# Microcontrolador.net
KiCad netlist of a schematic drawn in Altium Designer
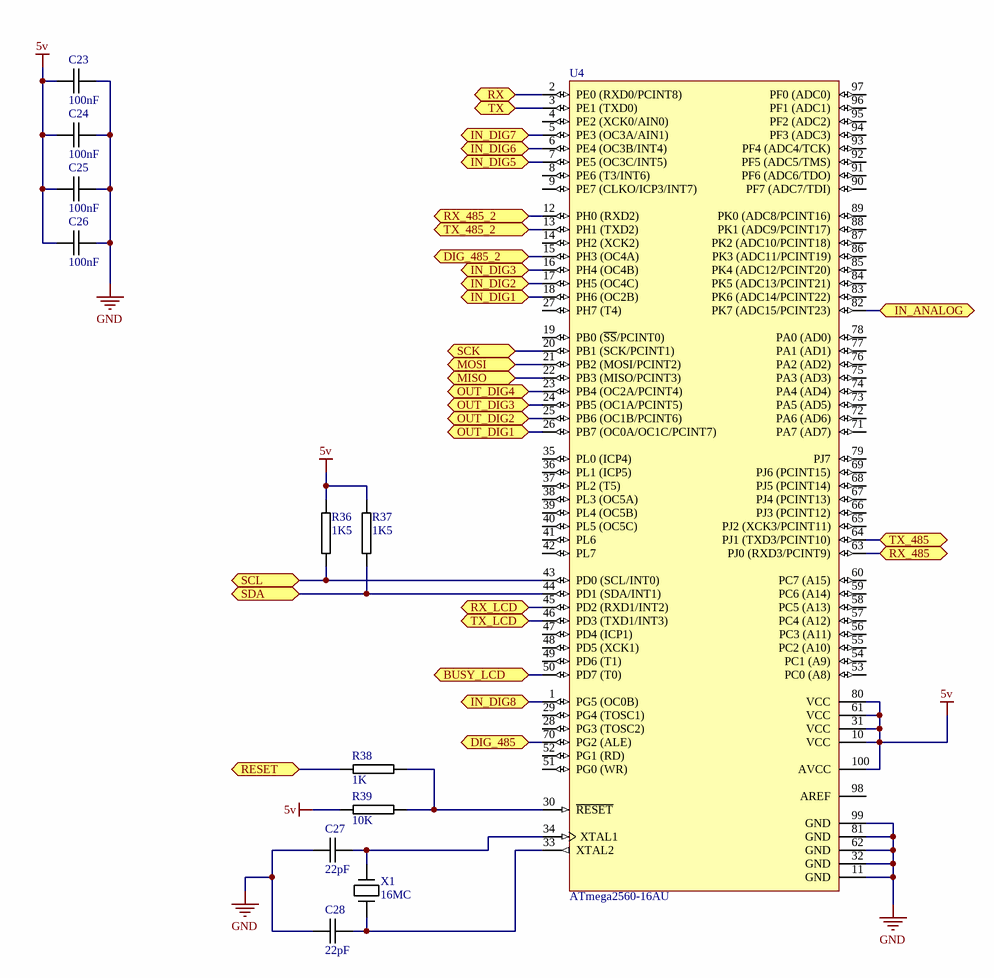
[diagram p0: Microcontrolador.SchDoc]

(export (version "E")
  (design (tool "Eeschema 10.0.6"))
  (components
    (comp (ref "C23")
      (value "100nF")
      (footprint "0805C-TBD")
      (description "CAPACITOR 0805 CERAMIC")
      (libsource (lib "vh_altium_library") (part "0805C-100nF-25V-X7R-MUR"))
    )
    (comp (ref "C24")
      (value "100nF")
      (footprint "0805C-TBD")
      (description "CAPACITOR 0805 CERAMIC")
      (libsource (lib "vh_altium_library") (part "0805C-100nF-25V-X7R-MUR"))
    )
    (comp (ref "C25")
      (value "100nF")
      (footprint "0805C-TBD")
      (description "CAPACITOR 0805 CERAMIC")
      (libsource (lib "vh_altium_library") (part "0805C-100nF-25V-X7R-MUR"))
    )
    (comp (ref "C26")
      (value "100nF")
      (footprint "0805C-TBD")
      (description "CAPACITOR 0805 CERAMIC")
      (libsource (lib "vh_altium_library") (part "0805C-100nF-25V-X7R-MUR"))
    )
    (comp (ref "C27")
      (value "22pF")
      (footprint "0603C-GENERIC")
      (description "CAPACITOR 0603 CERAMIC")
      (fields (field (name "TOLERANCE") "±5%") (field (name "MANUFACTURER PART NUMBER") "ECJ-1VC1H220J"))
      (libsource (lib "vh_altium_library") (part "0603C-22PF-50V-C0G-PAN"))
    )
    (comp (ref "C28")
      (value "22pF")
      (footprint "0603C-GENERIC")
      (description "CAPACITOR 0603 CERAMIC")
      (fields (field (name "TOLERANCE") "±5%") (field (name "MANUFACTURER PART NUMBER") "ECJ-1VC1H220J"))
      (libsource (lib "vh_altium_library") (part "0603C-22PF-50V-C0G-PAN"))
    )
    (comp (ref "R36")
      (value "1K5")
      (footprint "0805R-1K5")
      (description "RESISTOR 0805 1/4 WATT THIN FILM")
      (libsource (lib "vh_altium_library") (part "0805R-1K5"))
    )
    (comp (ref "R37")
      (value "1K5")
      (footprint "0805R-1K5")
      (description "RESISTOR 0805 1/4 WATT THIN FILM")
      (libsource (lib "vh_altium_library") (part "0805R-1K5"))
    )
    (comp (ref "R38")
      (value "1K")
      (footprint "0805R-1K")
      (description "RESISTOR 0805 1/4 WATT THIN FILM")
      (libsource (lib "vh_altium_library") (part "0805R-1K"))
    )
    (comp (ref "R39")
      (value "10K")
      (footprint "0805R-10K")
      (description "RESISTOR 0805 1/4 WATT THIN FILM")
      (libsource (lib "vh_altium_library") (part "0805R-10K"))
    )
    (comp (ref "U4")
      (value "ATmega2560-16AU")
      (footprint "100A_N")
      (libsource (lib "Atmel Microcontroller megaAVR") (part "ATmega2560-16AU"))
    )
    (comp (ref "X1")
      (value "16MC")
      (footprint "XTAL-RU49/4")
      (description "16MHZ CRSYTAL HC49US")
      (libsource (lib "vh_altium_library") (part "16MC-HC49US"))
    )
  )
  (nets
    (net (code "1") (name "/BUSY_LCD") (class "Default")
      (node (ref "U4") (pin "50") (pinfunction "PD7_(T0)_50") (pintype "bidirectional"))
    )
    (net (code "2") (name "/DIG_485") (class "Default")
      (node (ref "U4") (pin "70") (pinfunction "PG2_(ALE)_70") (pintype "bidirectional"))
    )
    (net (code "3") (name "/DIG_485_2") (class "Default")
      (node (ref "U4") (pin "15") (pinfunction "PH3_(OC4A)_15") (pintype "bidirectional"))
    )
    (net (code "4") (name "/IN_ANALOG") (class "Default")
      (node (ref "U4") (pin "82") (pinfunction "PK7_(ADC15/PCINT23)_82") (pintype "bidirectional"))
    )
    (net (code "5") (name "/IN_DIG1") (class "Default")
      (node (ref "U4") (pin "18") (pinfunction "PH6_(OC2B)_18") (pintype "bidirectional"))
    )
    (net (code "6") (name "/IN_DIG2") (class "Default")
      (node (ref "U4") (pin "17") (pinfunction "PH5_(OC4C)_17") (pintype "bidirectional"))
    )
    (net (code "7") (name "/IN_DIG3") (class "Default")
      (node (ref "U4") (pin "16") (pinfunction "PH4_(OC4B)_16") (pintype "bidirectional"))
    )
    (net (code "8") (name "/IN_DIG5") (class "Default")
      (node (ref "U4") (pin "7") (pinfunction "PE5_(OC3C/INT5)_7") (pintype "bidirectional"))
    )
    (net (code "9") (name "/IN_DIG6") (class "Default")
      (node (ref "U4") (pin "6") (pinfunction "PE4_(OC3B/INT4)_6") (pintype "bidirectional"))
    )
    (net (code "10") (name "/IN_DIG7") (class "Default")
      (node (ref "U4") (pin "5") (pinfunction "PE3_(OC3A/AIN1)_5") (pintype "bidirectional"))
    )
    (net (code "11") (name "/IN_DIG8") (class "Default")
      (node (ref "U4") (pin "1") (pinfunction "PG5_(OC0B)_1") (pintype "bidirectional"))
    )
    (net (code "12") (name "/MISO") (class "Default")
      (node (ref "U4") (pin "22") (pinfunction "PB3_(MISO/PCINT3)_22") (pintype "bidirectional"))
    )
    (net (code "13") (name "/MOSI") (class "Default")
      (node (ref "U4") (pin "21") (pinfunction "PB2_(MOSI/PCINT2)_21") (pintype "bidirectional"))
    )
    (net (code "14") (name "/OUT_DIG1") (class "Default")
      (node (ref "U4") (pin "26") (pinfunction "PB7_(OC0A/OC1C/PCINT7)_26") (pintype "bidirectional"))
    )
    (net (code "15") (name "/OUT_DIG2") (class "Default")
      (node (ref "U4") (pin "25") (pinfunction "PB6_(OC1B/PCINT6)_25") (pintype "bidirectional"))
    )
    (net (code "16") (name "/OUT_DIG3") (class "Default")
      (node (ref "U4") (pin "24") (pinfunction "PB5_(OC1A/PCINT5)_24") (pintype "bidirectional"))
    )
    (net (code "17") (name "/OUT_DIG4") (class "Default")
      (node (ref "U4") (pin "23") (pinfunction "PB4_(OC2A/PCINT4)_23") (pintype "bidirectional"))
    )
    (net (code "18") (name "/RESET") (class "Default") (node (ref "R38") (pin "1") (pintype "passive")))
    (net (code "19") (name "/RX") (class "Default")
      (node (ref "U4") (pin "2") (pinfunction "PE0_(RXD0/PCINT8)_2") (pintype "bidirectional"))
    )
    (net (code "20") (name "/RX_485") (class "Default")
      (node (ref "U4") (pin "63") (pinfunction "PJ0_(RXD3/PCINT9)_63") (pintype "bidirectional"))
    )
    (net (code "21") (name "/RX_485_2") (class "Default")
      (node (ref "U4") (pin "12") (pinfunction "PH0_(RXD2)_12") (pintype "bidirectional"))
    )
    (net (code "22") (name "/RX_LCD") (class "Default")
      (node (ref "U4") (pin "45") (pinfunction "PD2_(RXD1/INT2)_45") (pintype "bidirectional"))
    )
    (net (code "23") (name "/SCK") (class "Default")
      (node (ref "U4") (pin "20") (pinfunction "PB1_(SCK/PCINT1)_20") (pintype "bidirectional"))
    )
    (net (code "24") (name "/SCL") (class "Default")
      (node (ref "R36") (pin "2") (pintype "passive"))
      (node (ref "U4") (pin "43") (pinfunction "PD0_(SCL/INT0)_43") (pintype "bidirectional"))
    )
    (net (code "25") (name "/SDA") (class "Default")
      (node (ref "R37") (pin "2") (pintype "passive"))
      (node (ref "U4") (pin "44") (pinfunction "PD1_(SDA/INT1)_44") (pintype "bidirectional"))
    )
    (net (code "26") (name "/TX") (class "Default")
      (node (ref "U4") (pin "3") (pinfunction "PE1_(TXD0)_3") (pintype "bidirectional"))
    )
    (net (code "27") (name "/TX_485") (class "Default")
      (node (ref "U4") (pin "64") (pinfunction "PJ1_(TXD3/PCINT10)_64") (pintype "bidirectional"))
    )
    (net (code "28") (name "/TX_485_2") (class "Default")
      (node (ref "U4") (pin "13") (pinfunction "PH1_(TXD2)_13") (pintype "bidirectional"))
    )
    (net (code "29") (name "/TX_LCD") (class "Default")
      (node (ref "U4") (pin "46") (pinfunction "PD3_(TXD1/INT3)_46") (pintype "bidirectional"))
    )
    (net (code "30") (name "5v") (class "Default")
      (node (ref "C23") (pin "1") (pintype "passive"))
      (node (ref "C24") (pin "1") (pintype "passive"))
      (node (ref "C25") (pin "1") (pintype "passive"))
      (node (ref "C26") (pin "1") (pintype "passive"))
      (node (ref "R36") (pin "1") (pintype "passive"))
      (node (ref "R37") (pin "1") (pintype "passive"))
      (node (ref "R39") (pin "1") (pintype "passive"))
      (node (ref "U4") (pin "10") (pinfunction "VCC_10") (pintype "power_in"))
      (node (ref "U4") (pin "100") (pinfunction "AVCC_100") (pintype "power_in"))
      (node (ref "U4") (pin "31") (pinfunction "VCC_31") (pintype "power_in"))
      (node (ref "U4") (pin "61") (pinfunction "VCC_61") (pintype "power_in"))
      (node (ref "U4") (pin "80") (pinfunction "VCC_80") (pintype "power_in"))
    )
    (net (code "31") (name "GND") (class "Default")
      (node (ref "C23") (pin "2") (pintype "passive"))
      (node (ref "C24") (pin "2") (pintype "passive"))
      (node (ref "C25") (pin "2") (pintype "passive"))
      (node (ref "C26") (pin "2") (pintype "passive"))
      (node (ref "C27") (pin "1") (pintype "passive"))
      (node (ref "C28") (pin "1") (pintype "passive"))
      (node (ref "U4") (pin "11") (pinfunction "GND_11") (pintype "power_in"))
      (node (ref "U4") (pin "32") (pinfunction "GND_32") (pintype "power_in"))
      (node (ref "U4") (pin "62") (pinfunction "GND_62") (pintype "power_in"))
      (node (ref "U4") (pin "81") (pinfunction "GND_81") (pintype "power_in"))
      (node (ref "U4") (pin "99") (pinfunction "GND_99") (pintype "power_in"))
    )
    (net (code "32") (name "Net-(U4-XTAL1)") (class "Default")
      (node (ref "C27") (pin "2") (pintype "passive"))
      (node (ref "U4") (pin "34") (pinfunction "XTAL1_34") (pintype "input"))
      (node (ref "X1") (pin "1") (pintype "passive"))
    )
    (net (code "33") (name "Net-(U4-XTAL2)") (class "Default")
      (node (ref "C28") (pin "2") (pintype "passive"))
      (node (ref "U4") (pin "33") (pinfunction "XTAL2_33") (pintype "output"))
      (node (ref "X1") (pin "2") (pintype "passive"))
    )
    (net (code "34") (name "Net-(U4-~{RESET})") (class "Default")
      (node (ref "R38") (pin "2") (pintype "passive"))
      (node (ref "R39") (pin "2") (pintype "passive"))
      (node (ref "U4") (pin "30") (pinfunction "~{RESET}_30") (pintype "input"))
    )
    (net (code "35") (name "unconnected-(U4-AREF-Pad98)") (class "Default")
      (node (ref "U4") (pin "98") (pinfunction "AREF_98") (pintype "power_in"))
    )
    (net (code "36") (name "unconnected-(U4-PA0_(AD0)-Pad78)") (class "Default")
      (node (ref "U4") (pin "78") (pinfunction "PA0_(AD0)_78") (pintype "bidirectional"))
    )
    (net (code "37") (name "unconnected-(U4-PA1_(AD1)-Pad77)") (class "Default")
      (node (ref "U4") (pin "77") (pinfunction "PA1_(AD1)_77") (pintype "bidirectional"))
    )
    (net (code "38") (name "unconnected-(U4-PA2_(AD2)-Pad76)") (class "Default")
      (node (ref "U4") (pin "76") (pinfunction "PA2_(AD2)_76") (pintype "bidirectional"))
    )
    (net (code "39") (name "unconnected-(U4-PA3_(AD3)-Pad75)") (class "Default")
      (node (ref "U4") (pin "75") (pinfunction "PA3_(AD3)_75") (pintype "bidirectional"))
    )
    (net (code "40") (name "unconnected-(U4-PA4_(AD4)-Pad74)") (class "Default")
      (node (ref "U4") (pin "74") (pinfunction "PA4_(AD4)_74") (pintype "bidirectional"))
    )
    (net (code "41") (name "unconnected-(U4-PA5_(AD5)-Pad73)") (class "Default")
      (node (ref "U4") (pin "73") (pinfunction "PA5_(AD5)_73") (pintype "bidirectional"))
    )
    (net (code "42") (name "unconnected-(U4-PA6_(AD6)-Pad72)") (class "Default")
      (node (ref "U4") (pin "72") (pinfunction "PA6_(AD6)_72") (pintype "bidirectional"))
    )
    (net (code "43") (name "unconnected-(U4-PA7_(AD7)-Pad71)") (class "Default")
      (node (ref "U4") (pin "71") (pinfunction "PA7_(AD7)_71") (pintype "bidirectional"))
    )
    (net (code "44") (name "unconnected-(U4-PB0_(~{SS}{slash}PCINT0)-Pad19)") (class "Default")
      (node (ref "U4") (pin "19") (pinfunction "PB0_(~{SS}/PCINT0)_19") (pintype "bidirectional"))
    )
    (net (code "45") (name "unconnected-(U4-PC0_(A8)-Pad53)") (class "Default")
      (node (ref "U4") (pin "53") (pinfunction "PC0_(A8)_53") (pintype "bidirectional"))
    )
    (net (code "46") (name "unconnected-(U4-PC1_(A9)-Pad54)") (class "Default")
      (node (ref "U4") (pin "54") (pinfunction "PC1_(A9)_54") (pintype "bidirectional"))
    )
    (net (code "47") (name "unconnected-(U4-PC2_(A10)-Pad55)") (class "Default")
      (node (ref "U4") (pin "55") (pinfunction "PC2_(A10)_55") (pintype "bidirectional"))
    )
    (net (code "48") (name "unconnected-(U4-PC3_(A11)-Pad56)") (class "Default")
      (node (ref "U4") (pin "56") (pinfunction "PC3_(A11)_56") (pintype "bidirectional"))
    )
    (net (code "49") (name "unconnected-(U4-PC4_(A12)-Pad57)") (class "Default")
      (node (ref "U4") (pin "57") (pinfunction "PC4_(A12)_57") (pintype "bidirectional"))
    )
    (net (code "50") (name "unconnected-(U4-PC5_(A13)-Pad58)") (class "Default")
      (node (ref "U4") (pin "58") (pinfunction "PC5_(A13)_58") (pintype "bidirectional"))
    )
    (net (code "51") (name "unconnected-(U4-PC6_(A14)-Pad59)") (class "Default")
      (node (ref "U4") (pin "59") (pinfunction "PC6_(A14)_59") (pintype "bidirectional"))
    )
    (net (code "52") (name "unconnected-(U4-PC7_(A15)-Pad60)") (class "Default")
      (node (ref "U4") (pin "60") (pinfunction "PC7_(A15)_60") (pintype "bidirectional"))
    )
    (net (code "53") (name "unconnected-(U4-PD4_(ICP1)-Pad47)") (class "Default")
      (node (ref "U4") (pin "47") (pinfunction "PD4_(ICP1)_47") (pintype "bidirectional"))
    )
    (net (code "54") (name "unconnected-(U4-PD5_(XCK1)-Pad48)") (class "Default")
      (node (ref "U4") (pin "48") (pinfunction "PD5_(XCK1)_48") (pintype "bidirectional"))
    )
    (net (code "55") (name "unconnected-(U4-PD6_(T1)-Pad49)") (class "Default")
      (node (ref "U4") (pin "49") (pinfunction "PD6_(T1)_49") (pintype "bidirectional"))
    )
    (net (code "56") (name "unconnected-(U4-PE2_(XCK0{slash}AIN0)-Pad4)") (class "Default")
      (node (ref "U4") (pin "4") (pinfunction "PE2_(XCK0/AIN0)_4") (pintype "bidirectional"))
    )
    (net (code "57") (name "unconnected-(U4-PE6_(T3{slash}INT6)-Pad8)") (class "Default")
      (node (ref "U4") (pin "8") (pinfunction "PE6_(T3/INT6)_8") (pintype "bidirectional"))
    )
    (net (code "58") (name "unconnected-(U4-PE7_(CLKO{slash}ICP3{slash}INT7)-Pad9)") (class "Default")
      (node (ref "U4") (pin "9") (pinfunction "PE7_(CLKO/ICP3/INT7)_9") (pintype "bidirectional"))
    )
    (net (code "59") (name "unconnected-(U4-PF0_(ADC0)-Pad97)") (class "Default")
      (node (ref "U4") (pin "97") (pinfunction "PF0_(ADC0)_97") (pintype "bidirectional"))
    )
    (net (code "60") (name "unconnected-(U4-PF1_(ADC1)-Pad96)") (class "Default")
      (node (ref "U4") (pin "96") (pinfunction "PF1_(ADC1)_96") (pintype "bidirectional"))
    )
    (net (code "61") (name "unconnected-(U4-PF2_(ADC2)-Pad95)") (class "Default")
      (node (ref "U4") (pin "95") (pinfunction "PF2_(ADC2)_95") (pintype "bidirectional"))
    )
    (net (code "62") (name "unconnected-(U4-PF3_(ADC3)-Pad94)") (class "Default")
      (node (ref "U4") (pin "94") (pinfunction "PF3_(ADC3)_94") (pintype "bidirectional"))
    )
    (net (code "63") (name "unconnected-(U4-PF4_(ADC4{slash}TCK)-Pad93)") (class "Default")
      (node (ref "U4") (pin "93") (pinfunction "PF4_(ADC4/TCK)_93") (pintype "bidirectional"))
    )
    (net (code "64") (name "unconnected-(U4-PF5_(ADC5{slash}TMS)-Pad92)") (class "Default")
      (node (ref "U4") (pin "92") (pinfunction "PF5_(ADC5/TMS)_92") (pintype "bidirectional"))
    )
    (net (code "65") (name "unconnected-(U4-PF6_(ADC6{slash}TDO)-Pad91)") (class "Default")
      (node (ref "U4") (pin "91") (pinfunction "PF6_(ADC6/TDO)_91") (pintype "bidirectional"))
    )
    (net (code "66") (name "unconnected-(U4-PF7_(ADC7{slash}TDI)-Pad90)") (class "Default")
      (node (ref "U4") (pin "90") (pinfunction "PF7_(ADC7/TDI)_90") (pintype "bidirectional"))
    )
    (net (code "67") (name "unconnected-(U4-PG0_(WR)-Pad51)") (class "Default")
      (node (ref "U4") (pin "51") (pinfunction "PG0_(WR)_51") (pintype "bidirectional"))
    )
    (net (code "68") (name "unconnected-(U4-PG1_(RD)-Pad52)") (class "Default")
      (node (ref "U4") (pin "52") (pinfunction "PG1_(RD)_52") (pintype "bidirectional"))
    )
    (net (code "69") (name "unconnected-(U4-PG3_(TOSC2)-Pad28)") (class "Default")
      (node (ref "U4") (pin "28") (pinfunction "PG3_(TOSC2)_28") (pintype "bidirectional"))
    )
    (net (code "70") (name "unconnected-(U4-PG4_(TOSC1)-Pad29)") (class "Default")
      (node (ref "U4") (pin "29") (pinfunction "PG4_(TOSC1)_29") (pintype "bidirectional"))
    )
    (net (code "71") (name "unconnected-(U4-PH2_(XCK2)-Pad14)") (class "Default")
      (node (ref "U4") (pin "14") (pinfunction "PH2_(XCK2)_14") (pintype "bidirectional"))
    )
    (net (code "72") (name "unconnected-(U4-PH7_(T4)-Pad27)") (class "Default")
      (node (ref "U4") (pin "27") (pinfunction "PH7_(T4)_27") (pintype "bidirectional"))
    )
    (net (code "73") (name "unconnected-(U4-PJ2_(XCK3{slash}PCINT11)-Pad65)") (class "Default")
      (node (ref "U4") (pin "65") (pinfunction "PJ2_(XCK3/PCINT11)_65") (pintype "bidirectional"))
    )
    (net (code "74") (name "unconnected-(U4-PJ3_(PCINT12)-Pad66)") (class "Default")
      (node (ref "U4") (pin "66") (pinfunction "PJ3_(PCINT12)_66") (pintype "bidirectional"))
    )
    (net (code "75") (name "unconnected-(U4-PJ4_(PCINT13)-Pad67)") (class "Default")
      (node (ref "U4") (pin "67") (pinfunction "PJ4_(PCINT13)_67") (pintype "bidirectional"))
    )
    (net (code "76") (name "unconnected-(U4-PJ5_(PCINT14)-Pad68)") (class "Default")
      (node (ref "U4") (pin "68") (pinfunction "PJ5_(PCINT14)_68") (pintype "bidirectional"))
    )
    (net (code "77") (name "unconnected-(U4-PJ6_(PCINT15)-Pad69)") (class "Default")
      (node (ref "U4") (pin "69") (pinfunction "PJ6_(PCINT15)_69") (pintype "bidirectional"))
    )
    (net (code "78") (name "unconnected-(U4-PJ7-Pad79)") (class "Default")
      (node (ref "U4") (pin "79") (pinfunction "PJ7_79") (pintype "bidirectional"))
    )
    (net (code "79") (name "unconnected-(U4-PK0_(ADC8{slash}PCINT16)-Pad89)") (class "Default")
      (node (ref "U4") (pin "89") (pinfunction "PK0_(ADC8/PCINT16)_89") (pintype "bidirectional"))
    )
    (net (code "80") (name "unconnected-(U4-PK1_(ADC9{slash}PCINT17)-Pad88)") (class "Default")
      (node (ref "U4") (pin "88") (pinfunction "PK1_(ADC9/PCINT17)_88") (pintype "bidirectional"))
    )
    (net (code "81") (name "unconnected-(U4-PK2_(ADC10{slash}PCINT18)-Pad87)") (class "Default")
      (node (ref "U4") (pin "87") (pinfunction "PK2_(ADC10/PCINT18)_87") (pintype "bidirectional"))
    )
    (net (code "82") (name "unconnected-(U4-PK3_(ADC11{slash}PCINT19)-Pad86)") (class "Default")
      (node (ref "U4") (pin "86") (pinfunction "PK3_(ADC11/PCINT19)_86") (pintype "bidirectional"))
    )
    (net (code "83") (name "unconnected-(U4-PK4_(ADC12{slash}PCINT20)-Pad85)") (class "Default")
      (node (ref "U4") (pin "85") (pinfunction "PK4_(ADC12/PCINT20)_85") (pintype "bidirectional"))
    )
    (net (code "84") (name "unconnected-(U4-PK5_(ADC13{slash}PCINT21)-Pad84)") (class "Default")
      (node (ref "U4") (pin "84") (pinfunction "PK5_(ADC13/PCINT21)_84") (pintype "bidirectional"))
    )
    (net (code "85") (name "unconnected-(U4-PK6_(ADC14{slash}PCINT22)-Pad83)") (class "Default")
      (node (ref "U4") (pin "83") (pinfunction "PK6_(ADC14/PCINT22)_83") (pintype "bidirectional"))
    )
    (net (code "86") (name "unconnected-(U4-PL0_(ICP4)-Pad35)") (class "Default")
      (node (ref "U4") (pin "35") (pinfunction "PL0_(ICP4)_35") (pintype "bidirectional"))
    )
    (net (code "87") (name "unconnected-(U4-PL1_(ICP5)-Pad36)") (class "Default")
      (node (ref "U4") (pin "36") (pinfunction "PL1_(ICP5)_36") (pintype "bidirectional"))
    )
    (net (code "88") (name "unconnected-(U4-PL2_(T5)-Pad37)") (class "Default")
      (node (ref "U4") (pin "37") (pinfunction "PL2_(T5)_37") (pintype "bidirectional"))
    )
    (net (code "89") (name "unconnected-(U4-PL3_(OC5A)-Pad38)") (class "Default")
      (node (ref "U4") (pin "38") (pinfunction "PL3_(OC5A)_38") (pintype "bidirectional"))
    )
    (net (code "90") (name "unconnected-(U4-PL4_(OC5B)-Pad39)") (class "Default")
      (node (ref "U4") (pin "39") (pinfunction "PL4_(OC5B)_39") (pintype "bidirectional"))
    )
    (net (code "91") (name "unconnected-(U4-PL5_(OC5C)-Pad40)") (class "Default")
      (node (ref "U4") (pin "40") (pinfunction "PL5_(OC5C)_40") (pintype "bidirectional"))
    )
    (net (code "92") (name "unconnected-(U4-PL6-Pad41)") (class "Default")
      (node (ref "U4") (pin "41") (pinfunction "PL6_41") (pintype "bidirectional"))
    )
    (net (code "93") (name "unconnected-(U4-PL7-Pad42)") (class "Default")
      (node (ref "U4") (pin "42") (pinfunction "PL7_42") (pintype "bidirectional"))
    )
  )
)
